# 02-USER_IO.net
KiCad netlist of a schematic drawn in Altium Designer
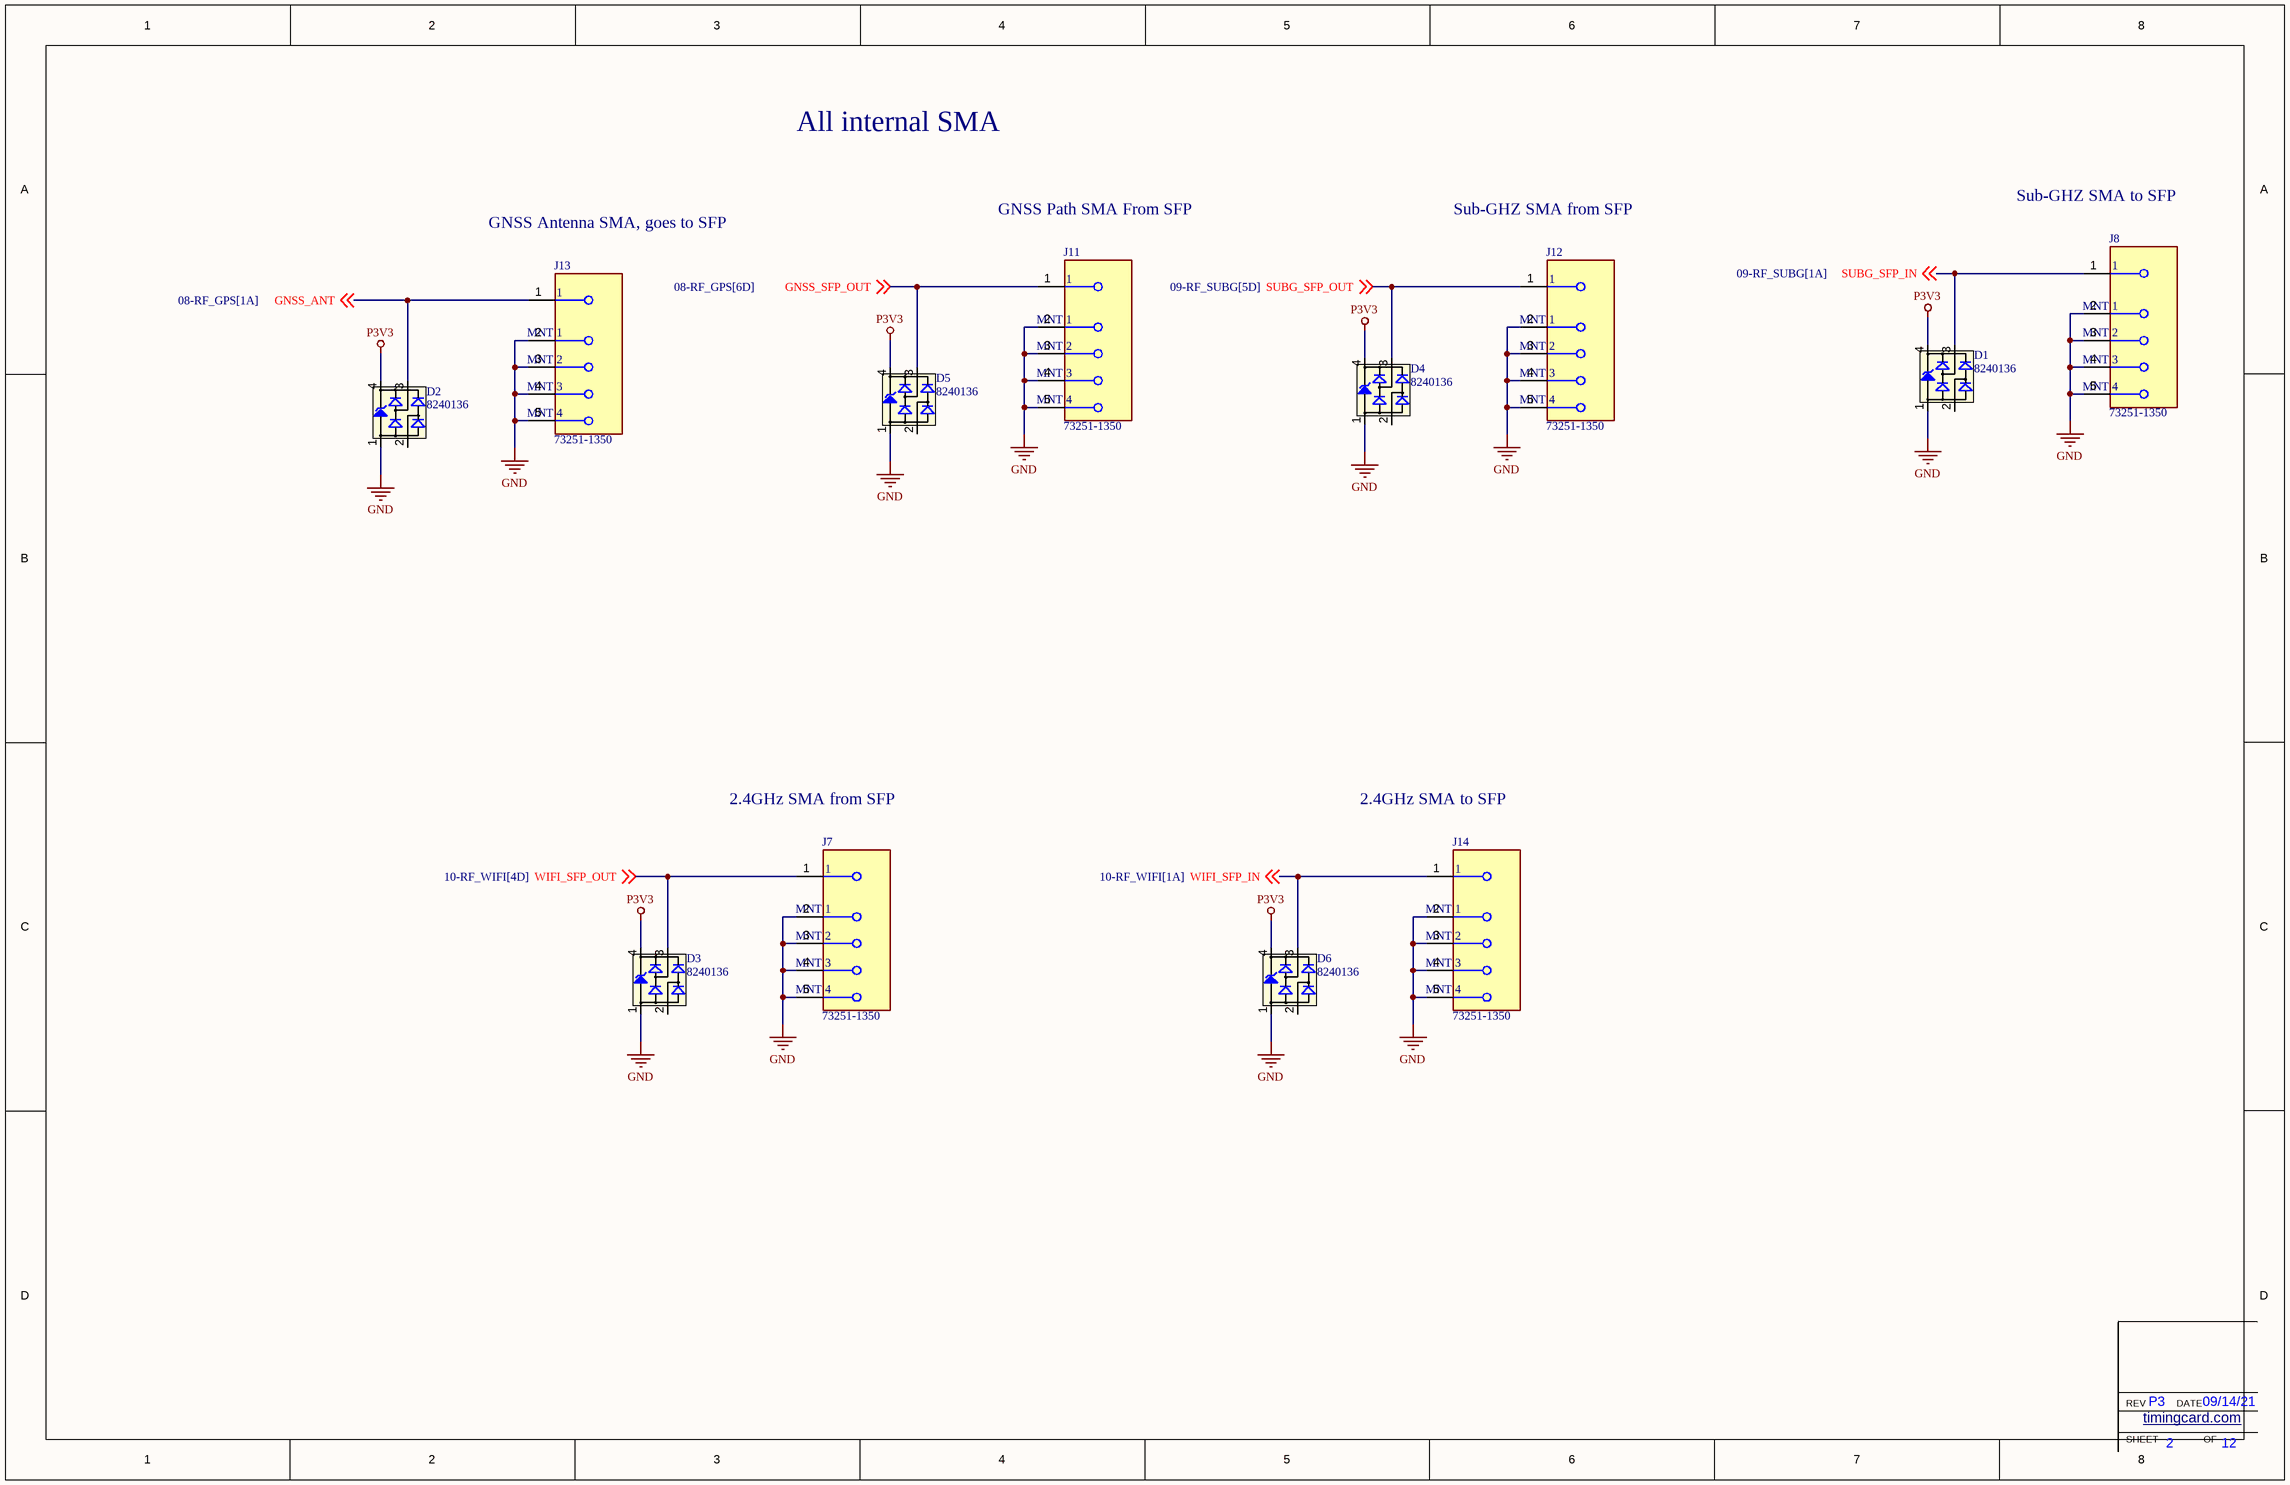
[diagram p0: 02-USER_IO.SchDoc]

(export (version "E")
  (design (tool "Eeschema 10.0.6"))
  (components
    (comp (ref "D1")
      (value "8240136")
      (footprint "SOT143-4L")
      (description "TVS Diode WE-TVS-HS, VRWM=3.3V")
      (fields (field (name "MANUFACTURER") "Wuerth Elektronik"))
      (libsource (lib "Altium Content Vault") (part "WE-TVS-HS-4"))
    )
    (comp (ref "D2")
      (value "8240136")
      (footprint "SOT143-4L")
      (description "TVS Diode WE-TVS-HS, VRWM=3.3V")
      (fields (field (name "MANUFACTURER") "Wuerth Elektronik"))
      (libsource (lib "Altium Content Vault") (part "WE-TVS-HS-4"))
    )
    (comp (ref "D3")
      (value "8240136")
      (footprint "SOT143-4L")
      (description "TVS Diode WE-TVS-HS, VRWM=3.3V")
      (fields (field (name "MANUFACTURER") "Wuerth Elektronik"))
      (libsource (lib "Altium Content Vault") (part "WE-TVS-HS-4"))
    )
    (comp (ref "D4")
      (value "8240136")
      (footprint "SOT143-4L")
      (description "TVS Diode WE-TVS-HS, VRWM=3.3V")
      (fields (field (name "MANUFACTURER") "Wuerth Elektronik"))
      (libsource (lib "Altium Content Vault") (part "WE-TVS-HS-4"))
    )
    (comp (ref "D5")
      (value "8240136")
      (footprint "SOT143-4L")
      (description "TVS Diode WE-TVS-HS, VRWM=3.3V")
      (fields (field (name "MANUFACTURER") "Wuerth Elektronik"))
      (libsource (lib "Altium Content Vault") (part "WE-TVS-HS-4"))
    )
    (comp (ref "D6")
      (value "8240136")
      (footprint "SOT143-4L")
      (description "TVS Diode WE-TVS-HS, VRWM=3.3V")
      (fields (field (name "MANUFACTURER") "Wuerth Elektronik"))
      (libsource (lib "Altium Content Vault") (part "WE-TVS-HS-4"))
    )
    (comp (ref "J7")
      (value "73251-1350")
      (footprint "FP-73251-1350-MFG")
      (description "CONN SMA JACK STR 50 OHM SMD")
      (fields
        (field (name "OCTOPART") "https://octopart.com/73251-1350-molex-5414390")
        (field (name "MANUFACTURER") "Molex")
      )
      (libsource (lib "Altium Content Vault") (part "474d33b8a96b1ade9ed6dd87a2b06d4"))
    )
    (comp (ref "J8")
      (value "73251-1350")
      (footprint "FP-73251-1350-MFG")
      (description "CONN SMA JACK STR 50 OHM SMD")
      (fields
        (field (name "OCTOPART") "https://octopart.com/73251-1350-molex-5414390")
        (field (name "MANUFACTURER") "Molex")
      )
      (libsource (lib "Altium Content Vault") (part "474d33b8a96b1ade9ed6dd87a2b06d4"))
    )
    (comp (ref "J11")
      (value "73251-1350")
      (footprint "FP-73251-1350-MFG")
      (description "CONN SMA JACK STR 50 OHM SMD")
      (fields
        (field (name "OCTOPART") "https://octopart.com/73251-1350-molex-5414390")
        (field (name "MANUFACTURER") "Molex")
      )
      (libsource (lib "Altium Content Vault") (part "474d33b8a96b1ade9ed6dd87a2b06d4"))
    )
    (comp (ref "J12")
      (value "73251-1350")
      (footprint "FP-73251-1350-MFG")
      (description "CONN SMA JACK STR 50 OHM SMD")
      (fields
        (field (name "OCTOPART") "https://octopart.com/73251-1350-molex-5414390")
        (field (name "MANUFACTURER") "Molex")
      )
      (libsource (lib "Altium Content Vault") (part "474d33b8a96b1ade9ed6dd87a2b06d4"))
    )
    (comp (ref "J13")
      (value "73251-1350")
      (footprint "FP-73251-1350-MFG")
      (description "CONN SMA JACK STR 50 OHM SMD")
      (fields
        (field (name "OCTOPART") "https://octopart.com/73251-1350-molex-5414390")
        (field (name "MANUFACTURER") "Molex")
      )
      (libsource (lib "Altium Content Vault") (part "474d33b8a96b1ade9ed6dd87a2b06d4"))
    )
    (comp (ref "J14")
      (value "73251-1350")
      (footprint "FP-73251-1350-MFG")
      (description "CONN SMA JACK STR 50 OHM SMD")
      (fields
        (field (name "OCTOPART") "https://octopart.com/73251-1350-molex-5414390")
        (field (name "MANUFACTURER") "Molex")
      )
      (libsource (lib "Altium Content Vault") (part "474d33b8a96b1ade9ed6dd87a2b06d4"))
    )
  )
  (nets
    (net (code "1") (name "GND") (class "Default")
      (node (ref "D1") (pin "1") (pinfunction "GND_1") (pintype "passive"))
      (node (ref "D2") (pin "1") (pinfunction "GND_1") (pintype "passive"))
      (node (ref "D3") (pin "1") (pinfunction "GND_1") (pintype "passive"))
      (node (ref "D4") (pin "1") (pinfunction "GND_1") (pintype "passive"))
      (node (ref "D5") (pin "1") (pinfunction "GND_1") (pintype "passive"))
      (node (ref "D6") (pin "1") (pinfunction "GND_1") (pintype "passive"))
      (node (ref "J11") (pin "2") (pinfunction "MNT_1_2") (pintype "passive"))
      (node (ref "J11") (pin "3") (pinfunction "MNT_2_3") (pintype "passive"))
      (node (ref "J11") (pin "4") (pinfunction "MNT_3_4") (pintype "passive"))
      (node (ref "J11") (pin "5") (pinfunction "MNT_4_5") (pintype "passive"))
      (node (ref "J12") (pin "2") (pinfunction "MNT_1_2") (pintype "passive"))
      (node (ref "J12") (pin "3") (pinfunction "MNT_2_3") (pintype "passive"))
      (node (ref "J12") (pin "4") (pinfunction "MNT_3_4") (pintype "passive"))
      (node (ref "J12") (pin "5") (pinfunction "MNT_4_5") (pintype "passive"))
      (node (ref "J13") (pin "2") (pinfunction "MNT_1_2") (pintype "passive"))
      (node (ref "J13") (pin "3") (pinfunction "MNT_2_3") (pintype "passive"))
      (node (ref "J13") (pin "4") (pinfunction "MNT_3_4") (pintype "passive"))
      (node (ref "J13") (pin "5") (pinfunction "MNT_4_5") (pintype "passive"))
      (node (ref "J14") (pin "2") (pinfunction "MNT_1_2") (pintype "passive"))
      (node (ref "J14") (pin "3") (pinfunction "MNT_2_3") (pintype "passive"))
      (node (ref "J14") (pin "4") (pinfunction "MNT_3_4") (pintype "passive"))
      (node (ref "J14") (pin "5") (pinfunction "MNT_4_5") (pintype "passive"))
      (node (ref "J7") (pin "2") (pinfunction "MNT_1_2") (pintype "passive"))
      (node (ref "J7") (pin "3") (pinfunction "MNT_2_3") (pintype "passive"))
      (node (ref "J7") (pin "4") (pinfunction "MNT_3_4") (pintype "passive"))
      (node (ref "J7") (pin "5") (pinfunction "MNT_4_5") (pintype "passive"))
      (node (ref "J8") (pin "2") (pinfunction "MNT_1_2") (pintype "passive"))
      (node (ref "J8") (pin "3") (pinfunction "MNT_2_3") (pintype "passive"))
      (node (ref "J8") (pin "4") (pinfunction "MNT_3_4") (pintype "passive"))
      (node (ref "J8") (pin "5") (pinfunction "MNT_4_5") (pintype "passive"))
    )
    (net (code "2") (name "GNSS_ANT") (class "Default")
      (node (ref "D2") (pin "3") (pinfunction "I/O2_3") (pintype "passive"))
      (node (ref "J13") (pin "1") (pinfunction "1_1") (pintype "passive"))
    )
    (net (code "3") (name "GNSS_SFP_OUT") (class "Default")
      (node (ref "D5") (pin "3") (pinfunction "I/O2_3") (pintype "passive"))
      (node (ref "J11") (pin "1") (pinfunction "1_1") (pintype "passive"))
    )
    (net (code "4") (name "P3V3") (class "Default")
      (node (ref "D1") (pin "4") (pinfunction "VDD_4") (pintype "passive"))
      (node (ref "D2") (pin "4") (pinfunction "VDD_4") (pintype "passive"))
      (node (ref "D3") (pin "4") (pinfunction "VDD_4") (pintype "passive"))
      (node (ref "D4") (pin "4") (pinfunction "VDD_4") (pintype "passive"))
      (node (ref "D5") (pin "4") (pinfunction "VDD_4") (pintype "passive"))
      (node (ref "D6") (pin "4") (pinfunction "VDD_4") (pintype "passive"))
    )
    (net (code "5") (name "SUBG_SFP_IN") (class "Default")
      (node (ref "D1") (pin "3") (pinfunction "I/O2_3") (pintype "passive"))
      (node (ref "J8") (pin "1") (pinfunction "1_1") (pintype "passive"))
    )
    (net (code "6") (name "SUBG_SFP_OUT") (class "Default")
      (node (ref "D4") (pin "3") (pinfunction "I/O2_3") (pintype "passive"))
      (node (ref "J12") (pin "1") (pinfunction "1_1") (pintype "passive"))
    )
    (net (code "7") (name "WIFI_SFP_IN") (class "Default")
      (node (ref "D6") (pin "3") (pinfunction "I/O2_3") (pintype "passive"))
      (node (ref "J14") (pin "1") (pinfunction "1_1") (pintype "passive"))
    )
    (net (code "8") (name "WIFI_SFP_OUT") (class "Default")
      (node (ref "D3") (pin "3") (pinfunction "I/O2_3") (pintype "passive"))
      (node (ref "J7") (pin "1") (pinfunction "1_1") (pintype "passive"))
    )
    (net (code "9") (name "unconnected-(D1-I{slash}O1-Pad2)") (class "Default")
      (node (ref "D1") (pin "2") (pinfunction "I/O1_2") (pintype "passive"))
    )
    (net (code "10") (name "unconnected-(D2-I{slash}O1-Pad2)") (class "Default")
      (node (ref "D2") (pin "2") (pinfunction "I/O1_2") (pintype "passive"))
    )
    (net (code "11") (name "unconnected-(D3-I{slash}O1-Pad2)") (class "Default")
      (node (ref "D3") (pin "2") (pinfunction "I/O1_2") (pintype "passive"))
    )
    (net (code "12") (name "unconnected-(D4-I{slash}O1-Pad2)") (class "Default")
      (node (ref "D4") (pin "2") (pinfunction "I/O1_2") (pintype "passive"))
    )
    (net (code "13") (name "unconnected-(D5-I{slash}O1-Pad2)") (class "Default")
      (node (ref "D5") (pin "2") (pinfunction "I/O1_2") (pintype "passive"))
    )
    (net (code "14") (name "unconnected-(D6-I{slash}O1-Pad2)") (class "Default")
      (node (ref "D6") (pin "2") (pinfunction "I/O1_2") (pintype "passive"))
    )
  )
)
